# lightmeter_seeed2.net
KiCad netlist of a schematic drawn in EAGLE
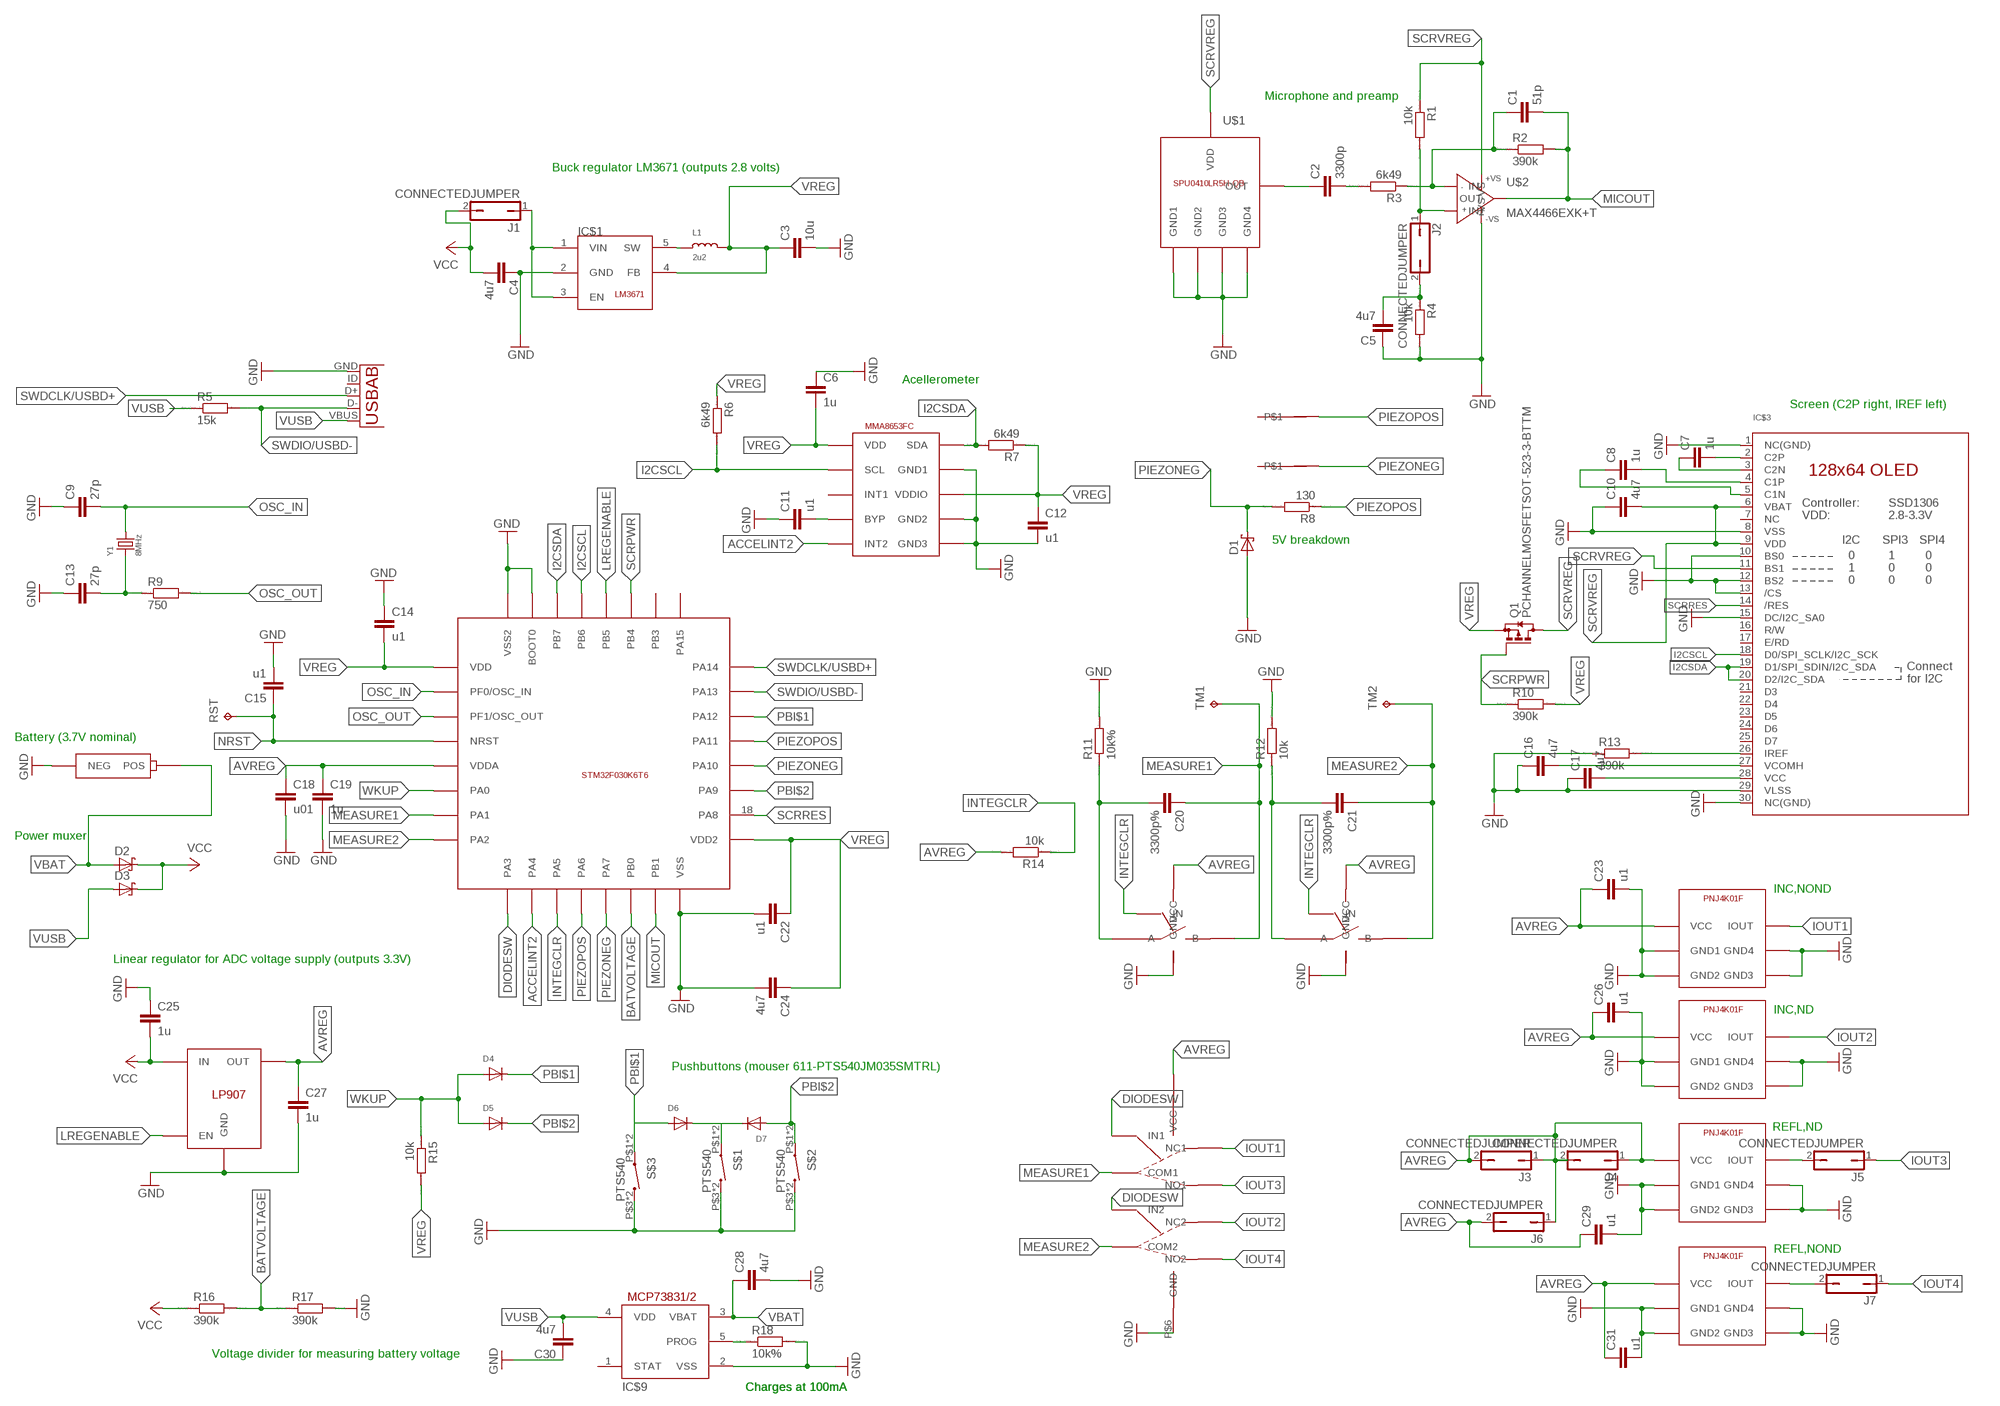
[diagram p0: schematic, sheet 1]

(export (version "E")
  (design (tool "Eeschema 10.0.6"))
  (components
    (comp (ref "C1")
      (value "51p")
      (footprint "eagle-import:C0402")
      (libsource (lib "eagle-import") (part "C-EUC0402"))
    )
    (comp (ref "C2")
      (value "3300p")
      (footprint "eagle-import:C0603")
      (libsource (lib "eagle-import") (part "C-EUC0603"))
    )
    (comp (ref "C3")
      (value "10u")
      (footprint "eagle-import:C0402")
      (libsource (lib "eagle-import") (part "C-EUC0402"))
    )
    (comp (ref "C4")
      (value "4u7")
      (footprint "eagle-import:C0402")
      (libsource (lib "eagle-import") (part "C-EUC0402"))
    )
    (comp (ref "C5")
      (value "4u7")
      (footprint "eagle-import:C0402")
      (libsource (lib "eagle-import") (part "C-EUC0402"))
    )
    (comp (ref "C6")
      (value "1u")
      (footprint "eagle-import:C0603")
      (libsource (lib "eagle-import") (part "C-EUC0603"))
    )
    (comp (ref "C7")
      (value "1u")
      (footprint "eagle-import:C0603")
      (libsource (lib "eagle-import") (part "C-EUC0603"))
    )
    (comp (ref "C8")
      (value "1u")
      (footprint "eagle-import:C0603")
      (libsource (lib "eagle-import") (part "C-EUC0603"))
    )
    (comp (ref "C9")
      (value "27p")
      (footprint "eagle-import:GAP0402")
      (libsource (lib "eagle-import") (part "CGAP0402"))
    )
    (comp (ref "C10")
      (value "4u7")
      (footprint "eagle-import:C0402")
      (libsource (lib "eagle-import") (part "C-EUC0402"))
    )
    (comp (ref "C11")
      (value "u1")
      (footprint "eagle-import:C0402")
      (libsource (lib "eagle-import") (part "C-EUC0402"))
    )
    (comp (ref "C12")
      (value "u1")
      (footprint "eagle-import:C0402")
      (libsource (lib "eagle-import") (part "C-EUC0402"))
    )
    (comp (ref "C13")
      (value "27p")
      (footprint "eagle-import:C0402")
      (libsource (lib "eagle-import") (part "C-EUC0402"))
    )
    (comp (ref "C14")
      (value "u1")
      (footprint "eagle-import:C0402")
      (libsource (lib "eagle-import") (part "C-EUC0402"))
    )
    (comp (ref "C15")
      (value "u1")
      (footprint "eagle-import:C0402")
      (libsource (lib "eagle-import") (part "C-EUC0402"))
    )
    (comp (ref "C16")
      (value "4u7")
      (footprint "eagle-import:C0402")
      (libsource (lib "eagle-import") (part "C-EUC0402"))
    )
    (comp (ref "C17")
      (value "4u7")
      (footprint "eagle-import:C0402")
      (libsource (lib "eagle-import") (part "C-EUC0402"))
    )
    (comp (ref "C18")
      (value "u01")
      (footprint "eagle-import:GAP0402")
      (libsource (lib "eagle-import") (part "CGAP0402"))
    )
    (comp (ref "C19")
      (value "1u")
      (footprint "eagle-import:GAP0603")
      (libsource (lib "eagle-import") (part "C"))
    )
    (comp (ref "C20")
      (value "3300p%")
      (footprint "eagle-import:C0603")
      (libsource (lib "eagle-import") (part "C-EUC0603"))
    )
    (comp (ref "C21")
      (value "3300p%")
      (footprint "eagle-import:C0603")
      (libsource (lib "eagle-import") (part "C-EUC0603"))
    )
    (comp (ref "C22")
      (value "u1")
      (footprint "eagle-import:C0402")
      (libsource (lib "eagle-import") (part "C-EUC0402"))
    )
    (comp (ref "C23")
      (value "u1")
      (footprint "eagle-import:C0402")
      (libsource (lib "eagle-import") (part "C-EUC0402"))
    )
    (comp (ref "C24")
      (value "4u7")
      (footprint "eagle-import:C0402")
      (libsource (lib "eagle-import") (part "C-EUC0402"))
    )
    (comp (ref "C25")
      (value "1u")
      (footprint "eagle-import:C0603")
      (libsource (lib "eagle-import") (part "C-EUC0603"))
    )
    (comp (ref "C26")
      (value "u1")
      (footprint "eagle-import:C0402")
      (libsource (lib "eagle-import") (part "C-EUC0402"))
    )
    (comp (ref "C27")
      (value "1u")
      (footprint "eagle-import:C0603")
      (libsource (lib "eagle-import") (part "C-EUC0603"))
    )
    (comp (ref "C28")
      (value "4u7")
      (footprint "eagle-import:C0402")
      (libsource (lib "eagle-import") (part "C-EUC0402"))
    )
    (comp (ref "C29")
      (value "u1")
      (footprint "eagle-import:C0402")
      (libsource (lib "eagle-import") (part "C-EUC0402"))
    )
    (comp (ref "C30")
      (value "4u7")
      (footprint "eagle-import:C0402")
      (libsource (lib "eagle-import") (part "C-EUC0402"))
    )
    (comp (ref "C31")
      (value "u1")
      (footprint "eagle-import:C0402")
      (libsource (lib "eagle-import") (part "C-EUC0402"))
    )
    (comp (ref "D1")
      (value "SCHOTTKY-DIODESOD-923-BTTM")
      (footprint "eagle-import:SOD-923-BTTM")
      (libsource (lib "eagle-import") (part "SCHOTTKY-DIODESOD-923-BTTM"))
    )
    (comp (ref "D2")
      (value "SCHOTTKY-DIODESC-79")
      (footprint "eagle-import:SC-79")
      (libsource (lib "eagle-import") (part "SCHOTTKY-DIODESC-79"))
    )
    (comp (ref "D3")
      (value "SCHOTTKY-DIODESC-79")
      (footprint "eagle-import:SC-79")
      (libsource (lib "eagle-import") (part "SCHOTTKY-DIODESC-79"))
    )
    (comp (ref "D4")
      (value "DIODESOD-323F")
      (footprint "eagle-import:SOD-323F")
      (libsource (lib "eagle-import") (part "DIODESOD-323F"))
    )
    (comp (ref "D5")
      (value "DIODESOD-323F")
      (footprint "eagle-import:SOD-323F")
      (libsource (lib "eagle-import") (part "DIODESOD-323F"))
    )
    (comp (ref "D6")
      (value "DIODESOD-323F")
      (footprint "eagle-import:SOD-323F")
      (libsource (lib "eagle-import") (part "DIODESOD-323F"))
    )
    (comp (ref "D7")
      (value "DIODESOD-323F")
      (footprint "eagle-import:SOD-323F")
      (libsource (lib "eagle-import") (part "DIODESOD-323F"))
    )
    (comp (ref "IC$1")
      (value "LM3671")
      (footprint "eagle-import:SOT23-5")
      (libsource (lib "eagle-import") (part "LM3671"))
    )
    (comp (ref "IC$2")
      (value "MMA8653")
      (footprint "eagle-import:DFN-10")
      (libsource (lib "eagle-import") (part "MMA8653"))
    )
    (comp (ref "IC$3")
      (value "DISP_OLED_UG-2864HSWEG010.96\"")
      (footprint "eagle-import:UG-2864HSWEG01_0.96IN_WRAPAROUND")
      (libsource (lib "eagle-import") (part "DISP_OLED_UG-2864HSWEG010.96{dblquote}"))
    )
    (comp (ref "IC$4")
      (value "STM32F030K6T6")
      (footprint "eagle-import:QFP-32")
      (libsource (lib "eagle-import") (part "STM32F030K6T6"))
    )
    (comp (ref "IC$5")
      (value "PNJ4K01F")
      (footprint "eagle-import:PNJ4K01F")
      (libsource (lib "eagle-import") (part "PNJ4K01F"))
    )
    (comp (ref "IC$6")
      (value "LP5907")
      (footprint "eagle-import:SOT23-5L")
      (libsource (lib "eagle-import") (part "LP5907"))
    )
    (comp (ref "IC$7")
      (value "PNJ4K01F")
      (footprint "eagle-import:PNJ4K01F")
      (libsource (lib "eagle-import") (part "PNJ4K01F"))
    )
    (comp (ref "IC$8")
      (value "PNJ4K01F")
      (footprint "eagle-import:PNJ4K01F")
      (libsource (lib "eagle-import") (part "PNJ4K01F"))
    )
    (comp (ref "IC$9")
      (value "MCP73831/OT")
      (footprint "eagle-import:SOT23-5L")
      (libsource (lib "eagle-import") (part "MCP73831/OT"))
    )
    (comp (ref "IC$10")
      (value "PNJ4K01F")
      (footprint "eagle-import:PNJ4K01F")
      (libsource (lib "eagle-import") (part "PNJ4K01F"))
    )
    (comp (ref "J1")
      (value "CONNECTEDJUMPER")
      (footprint "eagle-import:JUMPER_R0402")
      (libsource (lib "eagle-import") (part "CONNECTEDJUMPER"))
    )
    (comp (ref "J2")
      (value "CONNECTEDJUMPER")
      (footprint "eagle-import:JUMPER_R0402")
      (libsource (lib "eagle-import") (part "CONNECTEDJUMPER"))
    )
    (comp (ref "J3")
      (value "CONNECTEDJUMPER")
      (footprint "eagle-import:JUMPER_R0402")
      (libsource (lib "eagle-import") (part "CONNECTEDJUMPER"))
    )
    (comp (ref "J4")
      (value "CONNECTEDJUMPER")
      (footprint "eagle-import:JUMPER_R0402")
      (libsource (lib "eagle-import") (part "CONNECTEDJUMPER"))
    )
    (comp (ref "J5")
      (value "CONNECTEDJUMPER")
      (footprint "eagle-import:JUMPER_R0402")
      (libsource (lib "eagle-import") (part "CONNECTEDJUMPER"))
    )
    (comp (ref "J6")
      (value "CONNECTEDJUMPER")
      (footprint "eagle-import:JUMPER_R0402")
      (libsource (lib "eagle-import") (part "CONNECTEDJUMPER"))
    )
    (comp (ref "J7")
      (value "CONNECTEDJUMPER")
      (footprint "eagle-import:JUMPER_R0402")
      (libsource (lib "eagle-import") (part "CONNECTEDJUMPER"))
    )
    (comp (ref "L1")
      (value "2u2")
      (footprint "eagle-import:_0603")
      (libsource (lib "eagle-import") (part "INDUCTOR_0603"))
    )
    (comp (ref "Q1")
      (value "PCHANNELMOSFETSOT-523-3-BTTM")
      (footprint "eagle-import:SOT-523-3-BTTM")
      (libsource (lib "eagle-import") (part "PCHANNELMOSFETSOT-523-3-BTTM"))
    )
    (comp (ref "R1")
      (value "10k")
      (footprint "eagle-import:R0402")
      (libsource (lib "eagle-import") (part "R-EU_R0402"))
    )
    (comp (ref "R2")
      (value "390k")
      (footprint "eagle-import:R0402")
      (libsource (lib "eagle-import") (part "R-EU_R0402"))
    )
    (comp (ref "R3")
      (value "6k49")
      (footprint "eagle-import:R0402")
      (libsource (lib "eagle-import") (part "R-EU_R0402"))
    )
    (comp (ref "R4")
      (value "10k")
      (footprint "eagle-import:R0402")
      (libsource (lib "eagle-import") (part "R-EU_R0402"))
    )
    (comp (ref "R5")
      (value "15k")
      (footprint "eagle-import:R0402")
      (libsource (lib "eagle-import") (part "R-EU_R0402"))
    )
    (comp (ref "R6")
      (value "6k49")
      (footprint "eagle-import:R0402")
      (libsource (lib "eagle-import") (part "R-EU_R0402"))
    )
    (comp (ref "R7")
      (value "6k49")
      (footprint "eagle-import:R0402")
      (libsource (lib "eagle-import") (part "R-EU_R0402"))
    )
    (comp (ref "R8")
      (value "130")
      (footprint "eagle-import:R0402")
      (libsource (lib "eagle-import") (part "R-EU_R0402"))
    )
    (comp (ref "R9")
      (value "750")
      (footprint "eagle-import:R0402")
      (libsource (lib "eagle-import") (part "R-EU_R0402"))
    )
    (comp (ref "R10")
      (value "390k")
      (footprint "eagle-import:R0402")
      (libsource (lib "eagle-import") (part "R-EU_R0402"))
    )
    (comp (ref "R11")
      (value "10k%")
      (footprint "eagle-import:R0402")
      (libsource (lib "eagle-import") (part "R-EU_R0402"))
    )
    (comp (ref "R12")
      (value "10k")
      (footprint "eagle-import:R0402")
      (libsource (lib "eagle-import") (part "R-EU_R0402"))
    )
    (comp (ref "R13")
      (value "390k")
      (footprint "eagle-import:R0402")
      (libsource (lib "eagle-import") (part "R-EU_R0402"))
    )
    (comp (ref "R14")
      (value "10k")
      (footprint "eagle-import:R0402")
      (libsource (lib "eagle-import") (part "R-EU_R0402"))
    )
    (comp (ref "R15")
      (value "10k")
      (footprint "eagle-import:R0402")
      (libsource (lib "eagle-import") (part "R-EU_R0402"))
    )
    (comp (ref "R16")
      (value "390k")
      (footprint "eagle-import:JUMPER_R0402")
      (libsource (lib "eagle-import") (part "RGAP"))
    )
    (comp (ref "R17")
      (value "390k")
      (footprint "eagle-import:R0402")
      (libsource (lib "eagle-import") (part "R-EU_R0402"))
    )
    (comp (ref "R18")
      (value "10k%")
      (footprint "eagle-import:R0402")
      (libsource (lib "eagle-import") (part "R-EU_R0402"))
    )
    (comp (ref "RST")
      (value "TPB1,27")
      (footprint "eagle-import:B1,27")
      (libsource (lib "eagle-import") (part "TPB1,27"))
    )
    (comp (ref "S$1")
      (value "PTS540")
      (footprint "eagle-import:PTS540BTM")
      (libsource (lib "eagle-import") (part "PTS540"))
    )
    (comp (ref "S$2")
      (value "PTS540")
      (footprint "eagle-import:PTS540BTM")
      (libsource (lib "eagle-import") (part "PTS540"))
    )
    (comp (ref "S$3")
      (value "PTS540")
      (footprint "eagle-import:PTS540BTM")
      (libsource (lib "eagle-import") (part "PTS540"))
    )
    (comp (ref "TM1")
      (value "TPB1,27")
      (footprint "eagle-import:B1,27")
      (libsource (lib "eagle-import") (part "TPB1,27"))
    )
    (comp (ref "TM2")
      (value "TPB1,27")
      (footprint "eagle-import:B1,27")
      (libsource (lib "eagle-import") (part "TPB1,27"))
    )
    (comp (ref "U$1")
      (value "SPU0410LR5H-QBSPU0410LRSH-QB")
      (footprint "eagle-import:SPU0410LR5H-QB")
      (libsource (lib "eagle-import") (part "SPU0410LR5H-QBSPU0410LRSH-QB"))
    )
    (comp (ref "U$2")
      (value "MAX4466EXK+T")
      (footprint "eagle-import:SC-70-5")
      (libsource (lib "eagle-import") (part "MAX4466EXK+T"))
    )
    (comp (ref "U$3")
      (value "LIBAT")
      (footprint "eagle-import:78171-0002")
      (libsource (lib "eagle-import") (part "LIBAT"))
    )
    (comp (ref "U$4")
      (value "SN74LVC1G66")
      (footprint "eagle-import:SOT-553-5")
      (libsource (lib "eagle-import") (part "SN74LVC1G66"))
    )
    (comp (ref "U$5")
      (value "SN74LVC1G66")
      (footprint "eagle-import:SOT-553-5")
      (libsource (lib "eagle-import") (part "SN74LVC1G66"))
    )
    (comp (ref "U$6")
      (value "NLAS5223B")
      (footprint "eagle-import:WQFN10")
      (libsource (lib "eagle-import") (part "NLAS5223B"))
    )
    (comp (ref "U1")
      (value "USB-ABUSB-AB-MICRO-MIDMOUNT")
      (footprint "eagle-import:USB-AB-MICRO-MIDMOUNT")
      (libsource (lib "eagle-import") (part "USB-ABUSB-AB-MICRO-MIDMOUNT"))
    )
    (comp (ref "Y1")
      (value "8MHz")
      (footprint "eagle-import:CRYSTAL3.2X5MM")
      (libsource (lib "eagle-import") (part "CRYSTAL"))
    )
    (comp (ref "ZN")
      (value "WIREATTACHMENT")
      (footprint "eagle-import:SMALLSQUAREWIREHOLE")
      (libsource (lib "eagle-import") (part "WIREATTACHMENT"))
    )
    (comp (ref "ZP")
      (value "WIREATTACHMENT")
      (footprint "eagle-import:SMALLSQUAREWIREHOLE")
      (libsource (lib "eagle-import") (part "WIREATTACHMENT"))
    )
  )
  (nets
    (net (code "1") (name "ACCELINT2") (class "Default")
      (node (ref "IC$2") (pin "P$5") (pinfunction "INT2_P$5") (pintype "bidirectional"))
      (node (ref "IC$4") (pin "10") (pinfunction "PA4_10") (pintype "bidirectional"))
    )
    (net (code "2") (name "AVREG") (class "Default")
      (node (ref "C18") (pin "1") (pinfunction "1_1") (pintype "passive"))
      (node (ref "C19") (pin "1") (pinfunction "1_1") (pintype "passive"))
      (node (ref "C23") (pin "1") (pinfunction "1_1") (pintype "passive"))
      (node (ref "C26") (pin "1") (pinfunction "1_1") (pintype "passive"))
      (node (ref "C27") (pin "1") (pinfunction "1_1") (pintype "passive"))
      (node (ref "C29") (pin "1") (pinfunction "1_1") (pintype "passive"))
      (node (ref "C31") (pin "1") (pinfunction "1_1") (pintype "passive"))
      (node (ref "IC$10") (pin "P$1") (pinfunction "VCC_P$1") (pintype "bidirectional"))
      (node (ref "IC$4") (pin "5") (pinfunction "VDDA_5") (pintype "bidirectional"))
      (node (ref "IC$5") (pin "P$1") (pinfunction "VCC_P$1") (pintype "bidirectional"))
      (node (ref "IC$6") (pin "5") (pinfunction "OUT_5") (pintype "bidirectional"))
      (node (ref "IC$7") (pin "P$1") (pinfunction "VCC_P$1") (pintype "bidirectional"))
      (node (ref "IC$8") (pin "P$1") (pinfunction "VCC_P$1") (pintype "bidirectional"))
      (node (ref "J3") (pin "1") (pinfunction "1_1") (pintype "passive"))
      (node (ref "J3") (pin "2") (pinfunction "2_2") (pintype "passive"))
      (node (ref "J4") (pin "1") (pinfunction "1_1") (pintype "passive"))
      (node (ref "J4") (pin "2") (pinfunction "2_2") (pintype "passive"))
      (node (ref "J6") (pin "1") (pinfunction "1_1") (pintype "passive"))
      (node (ref "J6") (pin "2") (pinfunction "2_2") (pintype "passive"))
      (node (ref "R14") (pin "2") (pinfunction "2_2") (pintype "passive"))
      (node (ref "U$4") (pin "P$5") (pinfunction "VCC_P$5") (pintype "bidirectional"))
      (node (ref "U$5") (pin "P$5") (pinfunction "VCC_P$5") (pintype "bidirectional"))
      (node (ref "U$6") (pin "P$1") (pinfunction "VCC_P$1") (pintype "bidirectional"))
    )
    (net (code "3") (name "BATVOLTAGE") (class "Default")
      (node (ref "IC$4") (pin "14") (pinfunction "PB0_14") (pintype "bidirectional"))
      (node (ref "R16") (pin "2") (pinfunction "2_2") (pintype "passive"))
      (node (ref "R17") (pin "1") (pinfunction "1_1") (pintype "passive"))
    )
    (net (code "4") (name "DIODESW") (class "Default")
      (node (ref "IC$4") (pin "9") (pinfunction "PA3_9") (pintype "bidirectional"))
      (node (ref "U$6") (pin "P$4") (pinfunction "IN1_P$4") (pintype "bidirectional"))
      (node (ref "U$6") (pin "P$8") (pinfunction "IN2_P$8") (pintype "bidirectional"))
    )
    (net (code "5") (name "GND") (class "Default")
      (node (ref "C10") (pin "1") (pinfunction "1_1") (pintype "passive"))
      (node (ref "C11") (pin "1") (pinfunction "1_1") (pintype "passive"))
      (node (ref "C12") (pin "2") (pinfunction "2_2") (pintype "passive"))
      (node (ref "C13") (pin "1") (pinfunction "1_1") (pintype "passive"))
      (node (ref "C14") (pin "1") (pinfunction "1_1") (pintype "passive"))
      (node (ref "C15") (pin "2") (pinfunction "2_2") (pintype "passive"))
      (node (ref "C16") (pin "1") (pinfunction "1_1") (pintype "passive"))
      (node (ref "C17") (pin "1") (pinfunction "1_1") (pintype "passive"))
      (node (ref "C18") (pin "2") (pinfunction "2_2") (pintype "passive"))
      (node (ref "C19") (pin "2") (pinfunction "2_2") (pintype "passive"))
      (node (ref "C22") (pin "2") (pinfunction "2_2") (pintype "passive"))
      (node (ref "C23") (pin "2") (pinfunction "2_2") (pintype "passive"))
      (node (ref "C24") (pin "2") (pinfunction "2_2") (pintype "passive"))
      (node (ref "C25") (pin "1") (pinfunction "1_1") (pintype "passive"))
      (node (ref "C26") (pin "2") (pinfunction "2_2") (pintype "passive"))
      (node (ref "C27") (pin "2") (pinfunction "2_2") (pintype "passive"))
      (node (ref "C28") (pin "2") (pinfunction "2_2") (pintype "passive"))
      (node (ref "C29") (pin "2") (pinfunction "2_2") (pintype "passive"))
      (node (ref "C3") (pin "2") (pinfunction "2_2") (pintype "passive"))
      (node (ref "C30") (pin "1") (pinfunction "1_1") (pintype "passive"))
      (node (ref "C31") (pin "2") (pinfunction "2_2") (pintype "passive"))
      (node (ref "C4") (pin "1") (pinfunction "1_1") (pintype "passive"))
      (node (ref "C5") (pin "1") (pinfunction "1_1") (pintype "passive"))
      (node (ref "C6") (pin "1") (pinfunction "1_1") (pintype "passive"))
      (node (ref "C9") (pin "1") (pinfunction "1_1") (pintype "passive"))
      (node (ref "D1") (pin "P$1") (pinfunction "A_P$1") (pintype "passive"))
      (node (ref "IC$1") (pin "2") (pinfunction "GND_2") (pintype "bidirectional"))
      (node (ref "IC$10") (pin "P$2") (pinfunction "GND1_P$2") (pintype "bidirectional"))
      (node (ref "IC$10") (pin "P$3") (pinfunction "GND2_P$3") (pintype "bidirectional"))
      (node (ref "IC$10") (pin "P$4") (pinfunction "GND3_P$4") (pintype "bidirectional"))
      (node (ref "IC$10") (pin "P$5") (pinfunction "GND4_P$5") (pintype "bidirectional"))
      (node (ref "IC$2") (pin "P$6") (pinfunction "GND3_P$6") (pintype "bidirectional"))
      (node (ref "IC$2") (pin "P$7") (pinfunction "GND2_P$7") (pintype "bidirectional"))
      (node (ref "IC$2") (pin "P$9") (pinfunction "GND1_P$9") (pintype "bidirectional"))
      (node (ref "IC$3") (pin "1") (pinfunction "NC(GND)_1") (pintype "input"))
      (node (ref "IC$3") (pin "10") (pinfunction "BS0_10") (pintype "input"))
      (node (ref "IC$3") (pin "12") (pinfunction "BS2_12") (pintype "input"))
      (node (ref "IC$3") (pin "13") (pinfunction "/CS_13") (pintype "input"))
      (node (ref "IC$3") (pin "15") (pinfunction "DC/I2C_SA0_15") (pintype "input"))
      (node (ref "IC$3") (pin "29") (pinfunction "VLSS_29") (pintype "power_in"))
      (node (ref "IC$3") (pin "30") (pinfunction "NC(GND)_30") (pintype "input"))
      (node (ref "IC$3") (pin "8") (pinfunction "VSS_8") (pintype "power_in"))
      (node (ref "IC$4") (pin "16") (pinfunction "VSS_16") (pintype "bidirectional"))
      (node (ref "IC$4") (pin "31") (pinfunction "BOOT0_31") (pintype "bidirectional"))
      (node (ref "IC$4") (pin "32") (pinfunction "VSS2_32") (pintype "bidirectional"))
      (node (ref "IC$5") (pin "P$2") (pinfunction "GND1_P$2") (pintype "bidirectional"))
      (node (ref "IC$5") (pin "P$3") (pinfunction "GND2_P$3") (pintype "bidirectional"))
      (node (ref "IC$5") (pin "P$4") (pinfunction "GND3_P$4") (pintype "bidirectional"))
      (node (ref "IC$5") (pin "P$5") (pinfunction "GND4_P$5") (pintype "bidirectional"))
      (node (ref "IC$6") (pin "2") (pinfunction "GND_2") (pintype "bidirectional"))
      (node (ref "IC$7") (pin "P$2") (pinfunction "GND1_P$2") (pintype "bidirectional"))
      (node (ref "IC$7") (pin "P$3") (pinfunction "GND2_P$3") (pintype "bidirectional"))
      (node (ref "IC$7") (pin "P$4") (pinfunction "GND3_P$4") (pintype "bidirectional"))
      (node (ref "IC$7") (pin "P$5") (pinfunction "GND4_P$5") (pintype "bidirectional"))
      (node (ref "IC$8") (pin "P$2") (pinfunction "GND1_P$2") (pintype "bidirectional"))
      (node (ref "IC$8") (pin "P$3") (pinfunction "GND2_P$3") (pintype "bidirectional"))
      (node (ref "IC$8") (pin "P$4") (pinfunction "GND3_P$4") (pintype "bidirectional"))
      (node (ref "IC$8") (pin "P$5") (pinfunction "GND4_P$5") (pintype "bidirectional"))
      (node (ref "IC$9") (pin "2") (pinfunction "VSS_2") (pintype "power_in"))
      (node (ref "R11") (pin "2") (pinfunction "2_2") (pintype "passive"))
      (node (ref "R12") (pin "2") (pinfunction "2_2") (pintype "passive"))
      (node (ref "R13") (pin "1") (pinfunction "1_1") (pintype "passive"))
      (node (ref "R17") (pin "2") (pinfunction "2_2") (pintype "passive"))
      (node (ref "R18") (pin "2") (pinfunction "2_2") (pintype "passive"))
      (node (ref "R4") (pin "2") (pinfunction "2_2") (pintype "passive"))
      (node (ref "S$1") (pin "P$3") (pinfunction "2_P$3") (pintype "passive"))
      (node (ref "S$1") (pin "P$4") (pinfunction "2_P$4") (pintype "passive"))
      (node (ref "S$2") (pin "P$3") (pinfunction "2_P$3") (pintype "passive"))
      (node (ref "S$2") (pin "P$4") (pinfunction "2_P$4") (pintype "passive"))
      (node (ref "S$3") (pin "P$3") (pinfunction "2_P$3") (pintype "passive"))
      (node (ref "S$3") (pin "P$4") (pinfunction "2_P$4") (pintype "passive"))
      (node (ref "U$1") (pin "P$2") (pinfunction "GND1_P$2") (pintype "bidirectional"))
      (node (ref "U$1") (pin "P$3") (pinfunction "GND2_P$3") (pintype "bidirectional"))
      (node (ref "U$1") (pin "P$5") (pinfunction "GND3_P$5") (pintype "bidirectional"))
      (node (ref "U$1") (pin "P$6") (pinfunction "GND4_P$6") (pintype "bidirectional"))
      (node (ref "U$2") (pin "P$2") (pinfunction "-VS_P$2") (pintype "input"))
      (node (ref "U$3") (pin "P$1") (pinfunction "NEG_P$1") (pintype "bidirectional"))
      (node (ref "U$4") (pin "P$3") (pinfunction "GND_P$3") (pintype "bidirectional"))
      (node (ref "U$5") (pin "P$3") (pinfunction "GND_P$3") (pintype "bidirectional"))
      (node (ref "U$6") (pin "P$6") (pinfunction "GND_P$6") (pintype "bidirectional"))
      (node (ref "U1") (pin "GND") (pinfunction "GND_GND") (pintype "bidirectional"))
    )
    (net (code "6") (name "I2CSCL") (class "Default")
      (node (ref "IC$2") (pin "P$2") (pinfunction "SCL_P$2") (pintype "bidirectional"))
      (node (ref "IC$3") (pin "18") (pinfunction "D0/SPI_SCLK/I2C_SCK_18") (pintype "bidirectional"))
      (node (ref "IC$4") (pin "29") (pinfunction "PB6_29") (pintype "bidirectional"))
      (node (ref "R6") (pin "2") (pinfunction "2_2") (pintype "passive"))
    )
    (net (code "7") (name "I2CSDA") (class "Default")
      (node (ref "IC$2") (pin "P$10") (pinfunction "SDA_P$10") (pintype "bidirectional"))
      (node (ref "IC$3") (pin "19") (pinfunction "D1/SPI_SDIN/I2C_SDA_19") (pintype "bidirectional"))
      (node (ref "IC$3") (pin "20") (pinfunction "D2/I2C_SDA_20") (pintype "bidirectional"))
      (node (ref "IC$4") (pin "30") (pinfunction "PB7_30") (pintype "bidirectional"))
      (node (ref "R7") (pin "2") (pinfunction "2_2") (pintype "passive"))
    )
    (net (code "8") (name "INTEGCLR") (class "Default")
      (node (ref "IC$4") (pin "11") (pinfunction "PA5_11") (pintype "bidirectional"))
      (node (ref "R14") (pin "1") (pinfunction "1_1") (pintype "passive"))
      (node (ref "U$4") (pin "P$4") (pinfunction "IN_P$4") (pintype "bidirectional"))
      (node (ref "U$5") (pin "P$4") (pinfunction "IN_P$4") (pintype "bidirectional"))
    )
    (net (code "9") (name "IOUT1") (class "Default")
      (node (ref "IC$5") (pin "P$6") (pinfunction "IOUT_P$6") (pintype "bidirectional"))
      (node (ref "U$6") (pin "P$5") (pinfunction "NC1_P$5") (pintype "bidirectional"))
    )
    (net (code "10") (name "IOUT2") (class "Default")
      (node (ref "IC$7") (pin "P$6") (pinfunction "IOUT_P$6") (pintype "bidirectional"))
      (node (ref "U$6") (pin "P$7") (pinfunction "NC2_P$7") (pintype "bidirectional"))
    )
    (net (code "11") (name "IOUT3") (class "Default")
      (node (ref "J5") (pin "1") (pinfunction "1_1") (pintype "passive"))
      (node (ref "U$6") (pin "P$2") (pinfunction "NO1_P$2") (pintype "bidirectional"))
    )
    (net (code "12") (name "IOUT4") (class "Default")
      (node (ref "J7") (pin "1") (pinfunction "1_1") (pintype "passive"))
      (node (ref "U$6") (pin "P$10") (pinfunction "NO2_P$10") (pintype "bidirectional"))
    )
    (net (code "13") (name "LREGENABLE") (class "Default")
      (node (ref "IC$4") (pin "28") (pinfunction "PB5_28") (pintype "bidirectional"))
      (node (ref "IC$6") (pin "3") (pinfunction "EN_3") (pintype "bidirectional"))
    )
    (net (code "14") (name "MEASURE1") (class "Default")
      (node (ref "C20") (pin "1") (pinfunction "1_1") (pintype "passive"))
      (node (ref "IC$4") (pin "7") (pinfunction "PA1_7") (pintype "bidirectional"))
      (node (ref "TM1") (pin "TP") (pinfunction "TP_TP") (pintype "input"))
      (node (ref "U$4") (pin "P$2") (pinfunction "B_P$2") (pintype "bidirectional"))
      (node (ref "U$6") (pin "P$3") (pinfunction "COM1_P$3") (pintype "bidirectional"))
    )
    (net (code "15") (name "MEASURE2") (class "Default")
      (node (ref "C21") (pin "1") (pinfunction "1_1") (pintype "passive"))
      (node (ref "IC$4") (pin "8") (pinfunction "PA2_8") (pintype "bidirectional"))
      (node (ref "TM2") (pin "TP") (pinfunction "TP_TP") (pintype "input"))
      (node (ref "U$5") (pin "P$2") (pinfunction "B_P$2") (pintype "bidirectional"))
      (node (ref "U$6") (pin "P$9") (pinfunction "COM2_P$9") (pintype "bidirectional"))
    )
    (net (code "16") (name "MICOUT") (class "Default")
      (node (ref "C1") (pin "2") (pinfunction "2_2") (pintype "passive"))
      (node (ref "IC$4") (pin "15") (pinfunction "PB1_15") (pintype "bidirectional"))
      (node (ref "R2") (pin "2") (pinfunction "2_2") (pintype "passive"))
      (node (ref "U$2") (pin "P$4") (pinfunction "OUT_P$4") (pintype "output"))
    )
    (net (code "17") (name "NRST") (class "Default")
      (node (ref "C15") (pin "1") (pinfunction "1_1") (pintype "passive"))
      (node (ref "IC$4") (pin "4") (pinfunction "NRST_4") (pintype "bidirectional"))
      (node (ref "RST") (pin "TP") (pinfunction "TP_TP") (pintype "input"))
    )
    (net (code "18") (name "Net-(C2-Pad2)") (class "Default")
      (node (ref "C2") (pin "2") (pinfunction "2_2") (pintype "passive"))
      (node (ref "R3") (pin "2") (pinfunction "2_2") (pintype "passive"))
    )
    (net (code "19") (name "Net-(C5-Pad2)") (class "Default")
      (node (ref "C5") (pin "2") (pinfunction "2_2") (pintype "passive"))
      (node (ref "J2") (pin "2") (pinfunction "2_2") (pintype "passive"))
      (node (ref "R4") (pin "1") (pinfunction "1_1") (pintype "passive"))
    )
    (net (code "20") (name "Net-(D6-PadC)") (class "Default")
      (node (ref "D6") (pin "C") (pinfunction "C_C") (pintype "passive"))
      (node (ref "D7") (pin "C") (pinfunction "C_C") (pintype "passive"))
      (node (ref "S$1") (pin "P$1") (pinfunction "1_P$1") (pintype "passive"))
      (node (ref "S$1") (pin "P$2") (pinfunction "1_P$2") (pintype "passive"))
    )
    (net (code "21") (name "Net-(IC$1-EN)") (class "Default")
      (node (ref "IC$1") (pin "1") (pinfunction "VIN_1") (pintype "bidirectional"))
      (node (ref "IC$1") (pin "3") (pinfunction "EN_3") (pintype "bidirectional"))
      (node (ref "J1") (pin "1") (pinfunction "1_1") (pintype "passive"))
    )
    (net (code "22") (name "Net-(IC$1-SW)") (class "Default")
      (node (ref "IC$1") (pin "5") (pinfunction "SW_5") (pintype "bidirectional"))
      (node (ref "L1") (pin "1") (pinfunction "1_1") (pintype "passive"))
    )
    (net (code "23") (name "Net-(IC$2-BYP)") (class "Default")
      (node (ref "C11") (pin "2") (pinfunction "2_2") (pintype "passive"))
      (node (ref "IC$2") (pin "P$4") (pinfunction "BYP_P$4") (pintype "bidirectional"))
    )
    (net (code "24") (name "Net-(IC$3-C1N)") (class "Default")
      (node (ref "C8") (pin "1") (pinfunction "1_1") (pintype "passive"))
      (node (ref "IC$3") (pin "5") (pinfunction "C1N_5") (pintype "input"))
    )
    (net (code "25") (name "Net-(IC$3-C1P)") (class "Default")
      (node (ref "C8") (pin "2") (pinfunction "2_2") (pintype "passive"))
      (node (ref "IC$3") (pin "4") (pinfunction "C1P_4") (pintype "input"))
    )
    (net (code "26") (name "Net-(IC$3-C2N)") (class "Default")
      (node (ref "C7") (pin "1") (pinfunction "1_1") (pintype "passive"))
      (node (ref "IC$3") (pin "3") (pinfunction "C2N_3") (pintype "input"))
    )
    (net (code "27") (name "Net-(IC$3-C2P)") (class "Default")
      (node (ref "C7") (pin "2") (pinfunction "2_2") (pintype "passive"))
      (node (ref "IC$3") (pin "2") (pinfunction "C2P_2") (pintype "input"))
    )
    (net (code "28") (name "Net-(IC$3-IREF)") (class "Default")
      (node (ref "IC$3") (pin "26") (pinfunction "IREF_26") (pintype "input"))
      (node (ref "R13") (pin "2") (pinfunction "2_2") (pintype "passive"))
    )
    (net (code "29") (name "Net-(IC$3-VCC)") (class "Default")
      (node (ref "C17") (pin "2") (pinfunction "2_2") (pintype "passive"))
      (node (ref "IC$3") (pin "28") (pinfunction "VCC_28") (pintype "power_in"))
    )
    (net (code "30") (name "Net-(IC$3-VCOMH)") (class "Default")
      (node (ref "C16") (pin "2") (pinfunction "2_2") (pintype "passive"))
      (node (ref "IC$3") (pin "27") (pinfunction "VCOMH_27") (pintype "output"))
    )
    (net (code "31") (name "Net-(IC$8-IOUT)") (class "Default")
      (node (ref "IC$8") (pin "P$6") (pinfunction "IOUT_P$6") (pintype "bidirectional"))
      (node (ref "J5") (pin "2") (pinfunction "2_2") (pintype "passive"))
    )
    (net (code "32") (name "Net-(IC$9-PROG)") (class "Default")
      (node (ref "IC$9") (pin "5") (pinfunction "PROG_5") (pintype "input"))
      (node (ref "R18") (pin "1") (pinfunction "1_1") (pintype "passive"))
    )
    (net (code "33") (name "Net-(IC$10-IOUT)") (class "Default")
      (node (ref "IC$10") (pin "P$6") (pinfunction "IOUT_P$6") (pintype "bidirectional"))
      (node (ref "J7") (pin "2") (pinfunction "2_2") (pintype "passive"))
    )
    (net (code "34") (name "Net-(U$1-OUT)") (class "Default")
      (node (ref "C2") (pin "1") (pinfunction "1_1") (pintype "passive"))
      (node (ref "U$1") (pin "P$1") (pinfunction "OUT_P$1") (pintype "bidirectional"))
    )
    (net (code "35") (name "Net-(U$2-IN+)") (class "Default")
      (node (ref "J2") (pin "1") (pinfunction "1_1") (pintype "passive"))
      (node (ref "R1") (pin "2") (pinfunction "2_2") (pintype "passive"))
      (node (ref "U$2") (pin "P$1") (pinfunction "IN+_P$1") (pintype "input"))
    )
    (net (code "36") (name "Net-(U$2-IN-)") (class "Default")
      (node (ref "C1") (pin "1") (pinfunction "1_1") (pintype "passive"))
      (node (ref "R2") (pin "1") (pinfunction "1_1") (pintype "passive"))
      (node (ref "R3") (pin "1") (pinfunction "1_1") (pintype "passive"))
      (node (ref "U$2") (pin "P$3") (pinfunction "IN-_P$3") (pintype "input"))
    )
    (net (code "37") (name "Net-(U$4-A)") (class "Default")
      (node (ref "C20") (pin "2") (pinfunction "2_2") (pintype "passive"))
      (node (ref "R11") (pin "1") (pinfunction "1_1") (pintype "passive"))
      (node (ref "U$4") (pin "P$1") (pinfunction "A_P$1") (pintype "bidirectional"))
    )
    (net (code "38") (name "Net-(U$5-A)") (class "Default")
      (node (ref "C21") (pin "2") (pinfunction "2_2") (pintype "passive"))
      (node (ref "R12") (pin "1") (pinfunction "1_1") (pintype "passive"))
      (node (ref "U$5") (pin "P$1") (pinfunction "A_P$1") (pintype "bidirectional"))
    )
    (net (code "39") (name "Net-(Y1-1)") (class "Default")
      (node (ref "C13") (pin "2") (pinfunction "2_2") (pintype "passive"))
      (node (ref "R9") (pin "1") (pinfunction "1_1") (pintype "passive"))
      (node (ref "Y1") (pin "P$1") (pinfunction "1_P$1") (pintype "passive"))
    )
    (net (code "40") (name "OSC_IN") (class "Default")
      (node (ref "C9") (pin "2") (pinfunction "2_2") (pintype "passive"))
      (node (ref "IC$4") (pin "2") (pinfunction "PF0/OSC_IN_2") (pintype "bidirectional"))
      (node (ref "Y1") (pin "P$2") (pinfunction "2_P$2") (pintype "passive"))
    )
    (net (code "41") (name "OSC_OUT") (class "Default")
      (node (ref "IC$4") (pin "3") (pinfunction "PF1/OSC_OUT_3") (pintype "bidirectional"))
      (node (ref "R9") (pin "2") (pinfunction "2_2") (pintype "passive"))
    )
    (net (code "42") (name "PBI$1") (class "Default")
      (node (ref "D4") (pin "C") (pinfunction "C_C") (pintype "passive"))
      (node (ref "D6") (pin "A") (pinfunction "A_A") (pintype "passive"))
      (node (ref "IC$4") (pin "22") (pinfunction "PA12_22") (pintype "bidirectional"))
      (node (ref "S$3") (pin "P$1") (pinfunction "1_P$1") (pintype "passive"))
      (node (ref "S$3") (pin "P$2") (pinfunction "1_P$2") (pintype "passive"))
    )
    (net (code "43") (name "PBI$2") (class "Default")
      (node (ref "D5") (pin "C") (pinfunction "C_C") (pintype "passive"))
      (node (ref "D7") (pin "A") (pinfunction "A_A") (pintype "passive"))
      (node (ref "IC$4") (pin "19") (pinfunction "PA9_19") (pintype "bidirectional"))
      (node (ref "S$2") (pin "P$1") (pinfunction "1_P$1") (pintype "passive"))
      (node (ref "S$2") (pin "P$2") (pinfunction "1_P$2") (pintype "passive"))
    )
    (net (code "44") (name "PIEZONEG") (class "Default")
      (node (ref "D1") (pin "P$2") (pinfunction "C_P$2") (pintype "passive"))
      (node (ref "IC$4") (pin "13") (pinfunction "PA7_13") (pintype "bidirectional"))
      (node (ref "IC$4") (pin "20") (pinfunction "PA10_20") (pintype "bidirectional"))
      (node (ref "R8") (pin "2") (pinfunction "2_2") (pintype "passive"))
      (node (ref "ZN") (pin "P$1") (pinfunction "P$1_P$1") (pintype "bidirectional"))
    )
    (net (code "45") (name "PIEZOPOS") (class "Default")
      (node (ref "IC$4") (pin "12") (pinfunction "PA6_12") (pintype "bidirectional"))
      (node (ref "IC$4") (pin "21") (pinfunction "PA11_21") (pintype "bidirectional"))
      (node (ref "R8") (pin "1") (pinfunction "1_1") (pintype "passive"))
      (node (ref "ZP") (pin "P$1") (pinfunction "P$1_P$1") (pintype "bidirectional"))
    )
    (net (code "46") (name "SCRPWR") (class "Default")
      (node (ref "IC$4") (pin "27") (pinfunction "PB4_27") (pintype "bidirectional"))
      (node (ref "Q1") (pin "P$2") (pinfunction "G_P$2") (pintype "passive"))
      (node (ref "R10") (pin "1") (pinfunction "1_1") (pintype "passive"))
    )
    (net (code "47") (name "SCRRES") (class "Default")
      (node (ref "IC$3") (pin "14") (pinfunction "/RES_14") (pintype "input"))
      (node (ref "IC$4") (pin "18") (pinfunction "PA8_18") (pintype "bidirectional"))
    )
    (net (code "48") (name "SCRVREG") (class "Default")
      (node (ref "C10") (pin "2") (pinfunction "2_2") (pintype "passive"))
      (node (ref "IC$3") (pin "11") (pinfunction "BS1_11") (pintype "input"))
      (node (ref "IC$3") (pin "6") (pinfunction "VBAT_6") (pintype "input"))
      (node (ref "IC$3") (pin "9") (pinfunction "VDD_9") (pintype "power_in"))
      (node (ref "Q1") (pin "P$1") (pinfunction "D_P$1") (pintype "passive"))
      (node (ref "R1") (pin "1") (pinfunction "1_1") (pintype "passive"))
      (node (ref "U$1") (pin "P$4") (pinfunction "VDD_P$4") (pintype "bidirectional"))
      (node (ref "U$2") (pin "P$5") (pinfunction "+VS_P$5") (pintype "input"))
    )
    (net (code "49") (name "SWDCLK{slash}USBD+") (class "Default")
      (node (ref "IC$4") (pin "24") (pinfunction "PA14_24") (pintype "bidirectional"))
      (node (ref "U1") (pin "D+") (pinfunction "D+_D+") (pintype "bidirectional"))
    )
    (net (code "50") (name "SWDIO{slash}USBD-") (class "Default")
      (node (ref "IC$4") (pin "23") (pinfunction "PA13_23") (pintype "bidirectional"))
      (node (ref "R5") (pin "2") (pinfunction "2_2") (pintype "passive"))
      (node (ref "U1") (pin "D-") (pinfunction "D-_D-") (pintype "bidirectional"))
    )
    (net (code "51") (name "VBAT") (class "Default")
      (node (ref "C28") (pin "1") (pinfunction "1_1") (pintype "passive"))
      (node (ref "D2") (pin "P$2") (pinfunction "A_P$2") (pintype "passive"))
      (node (ref "IC$9") (pin "3") (pinfunction "VBAT_3") (pintype "bidirectional"))
      (node (ref "U$3") (pin "P$2") (pinfunction "POS_P$2") (pintype "bidirectional"))
    )
    (net (code "52") (name "VCC") (class "Default")
      (node (ref "C25") (pin "2") (pinfunction "2_2") (pintype "passive"))
      (node (ref "C4") (pin "2") (pinfunction "2_2") (pintype "passive"))
      (node (ref "D2") (pin "P$1") (pinfunction "C_P$1") (pintype "passive"))
      (node (ref "D3") (pin "P$1") (pinfunction "C_P$1") (pintype "passive"))
      (node (ref "IC$6") (pin "1") (pinfunction "IN_1") (pintype "bidirectional"))
      (node (ref "J1") (pin "2") (pinfunction "2_2") (pintype "passive"))
      (node (ref "R16") (pin "1") (pinfunction "1_1") (pintype "passive"))
    )
    (net (code "53") (name "VREG") (class "Default")
      (node (ref "C12") (pin "1") (pinfunction "1_1") (pintype "passive"))
      (node (ref "C14") (pin "2") (pinfunction "2_2") (pintype "passive"))
      (node (ref "C22") (pin "1") (pinfunction "1_1") (pintype "passive"))
      (node (ref "C24") (pin "1") (pinfunction "1_1") (pintype "passive"))
      (node (ref "C3") (pin "1") (pinfunction "1_1") (pintype "passive"))
      (node (ref "C6") (pin "2") (pinfunction "2_2") (pintype "passive"))
      (node (ref "IC$1") (pin "4") (pinfunction "FB_4") (pintype "bidirectional"))
      (node (ref "IC$2") (pin "P$1") (pinfunction "VDD_P$1") (pintype "bidirectional"))
      (node (ref "IC$2") (pin "P$8") (pinfunction "VDDIO_P$8") (pintype "bidirectional"))
      (node (ref "IC$4") (pin "1") (pinfunction "VDD_1") (pintype "bidirectional"))
      (node (ref "IC$4") (pin "17") (pinfunction "VDD2_17") (pintype "bidirectional"))
      (node (ref "L1") (pin "2") (pinfunction "2_2") (pintype "passive"))
      (node (ref "Q1") (pin "P$3") (pinfunction "S_P$3") (pintype "passive"))
      (node (ref "R10") (pin "2") (pinfunction "2_2") (pintype "passive"))
      (node (ref "R15") (pin "2") (pinfunction "2_2") (pintype "passive"))
      (node (ref "R6") (pin "1") (pinfunction "1_1") (pintype "passive"))
      (node (ref "R7") (pin "1") (pinfunction "1_1") (pintype "passive"))
    )
    (net (code "54") (name "VUSB") (class "Default")
      (node (ref "C30") (pin "2") (pinfunction "2_2") (pintype "passive"))
      (node (ref "D3") (pin "P$2") (pinfunction "A_P$2") (pintype "passive"))
      (node (ref "IC$9") (pin "4") (pinfunction "VDD_4") (pintype "power_in"))
      (node (ref "R5") (pin "1") (pinfunction "1_1") (pintype "passive"))
      (node (ref "U1") (pin "VBUS") (pinfunction "VBUS_VBUS") (pintype "bidirectional"))
    )
    (net (code "55") (name "WKUP") (class "Default")
      (node (ref "D4") (pin "A") (pinfunction "A_A") (pintype "passive"))
      (node (ref "D5") (pin "A") (pinfunction "A_A") (pintype "passive"))
      (node (ref "IC$4") (pin "6") (pinfunction "PA0_6") (pintype "bidirectional"))
      (node (ref "R15") (pin "1") (pinfunction "1_1") (pintype "passive"))
    )
    (net (code "56") (name "unconnected-(IC$2-INT1-PadP$3)") (class "Default")
      (node (ref "IC$2") (pin "P$3") (pinfunction "INT1_P$3") (pintype "bidirectional"))
    )
    (net (code "57") (name "unconnected-(IC$3-D3-Pad21)") (class "Default")
      (node (ref "IC$3") (pin "21") (pinfunction "D3_21") (pintype "bidirectional"))
    )
    (net (code "58") (name "unconnected-(IC$3-D4-Pad22)") (class "Default")
      (node (ref "IC$3") (pin "22") (pinfunction "D4_22") (pintype "bidirectional"))
    )
    (net (code "59") (name "unconnected-(IC$3-D5-Pad23)") (class "Default")
      (node (ref "IC$3") (pin "23") (pinfunction "D5_23") (pintype "bidirectional"))
    )
    (net (code "60") (name "unconnected-(IC$3-D6-Pad24)") (class "Default")
      (node (ref "IC$3") (pin "24") (pinfunction "D6_24") (pintype "bidirectional"))
    )
    (net (code "61") (name "unconnected-(IC$3-D7-Pad25)") (class "Default")
      (node (ref "IC$3") (pin "25") (pinfunction "D7_25") (pintype "bidirectional"))
    )
    (net (code "62") (name "unconnected-(IC$3-E{slash}RD-Pad17)") (class "Default")
      (node (ref "IC$3") (pin "17") (pinfunction "E/RD_17") (pintype "input"))
    )
    (net (code "63") (name "unconnected-(IC$3-NC-Pad7)") (class "Default")
      (node (ref "IC$3") (pin "7") (pinfunction "NC_7") (pintype "no_connect"))
    )
    (net (code "64") (name "unconnected-(IC$3-R{slash}W-Pad16)") (class "Default")
      (node (ref "IC$3") (pin "16") (pinfunction "R/W_16") (pintype "input"))
    )
    (net (code "65") (name "unconnected-(IC$4-PA15-Pad25)") (class "Default")
      (node (ref "IC$4") (pin "25") (pinfunction "PA15_25") (pintype "bidirectional"))
    )
    (net (code "66") (name "unconnected-(IC$4-PB3-Pad26)") (class "Default")
      (node (ref "IC$4") (pin "26") (pinfunction "PB3_26") (pintype "bidirectional"))
    )
    (net (code "67") (name "unconnected-(IC$9-STAT-Pad1)") (class "Default")
      (node (ref "IC$9") (pin "1") (pinfunction "STAT_1") (pintype "output"))
    )
    (net (code "68") (name "unconnected-(U1-USBID-PadID)") (class "Default")
      (node (ref "U1") (pin "ID") (pinfunction "USBID_ID") (pintype "bidirectional"))
    )
  )
)
